# untitled.net
KiCad netlist of a schematic drawn in EAGLE
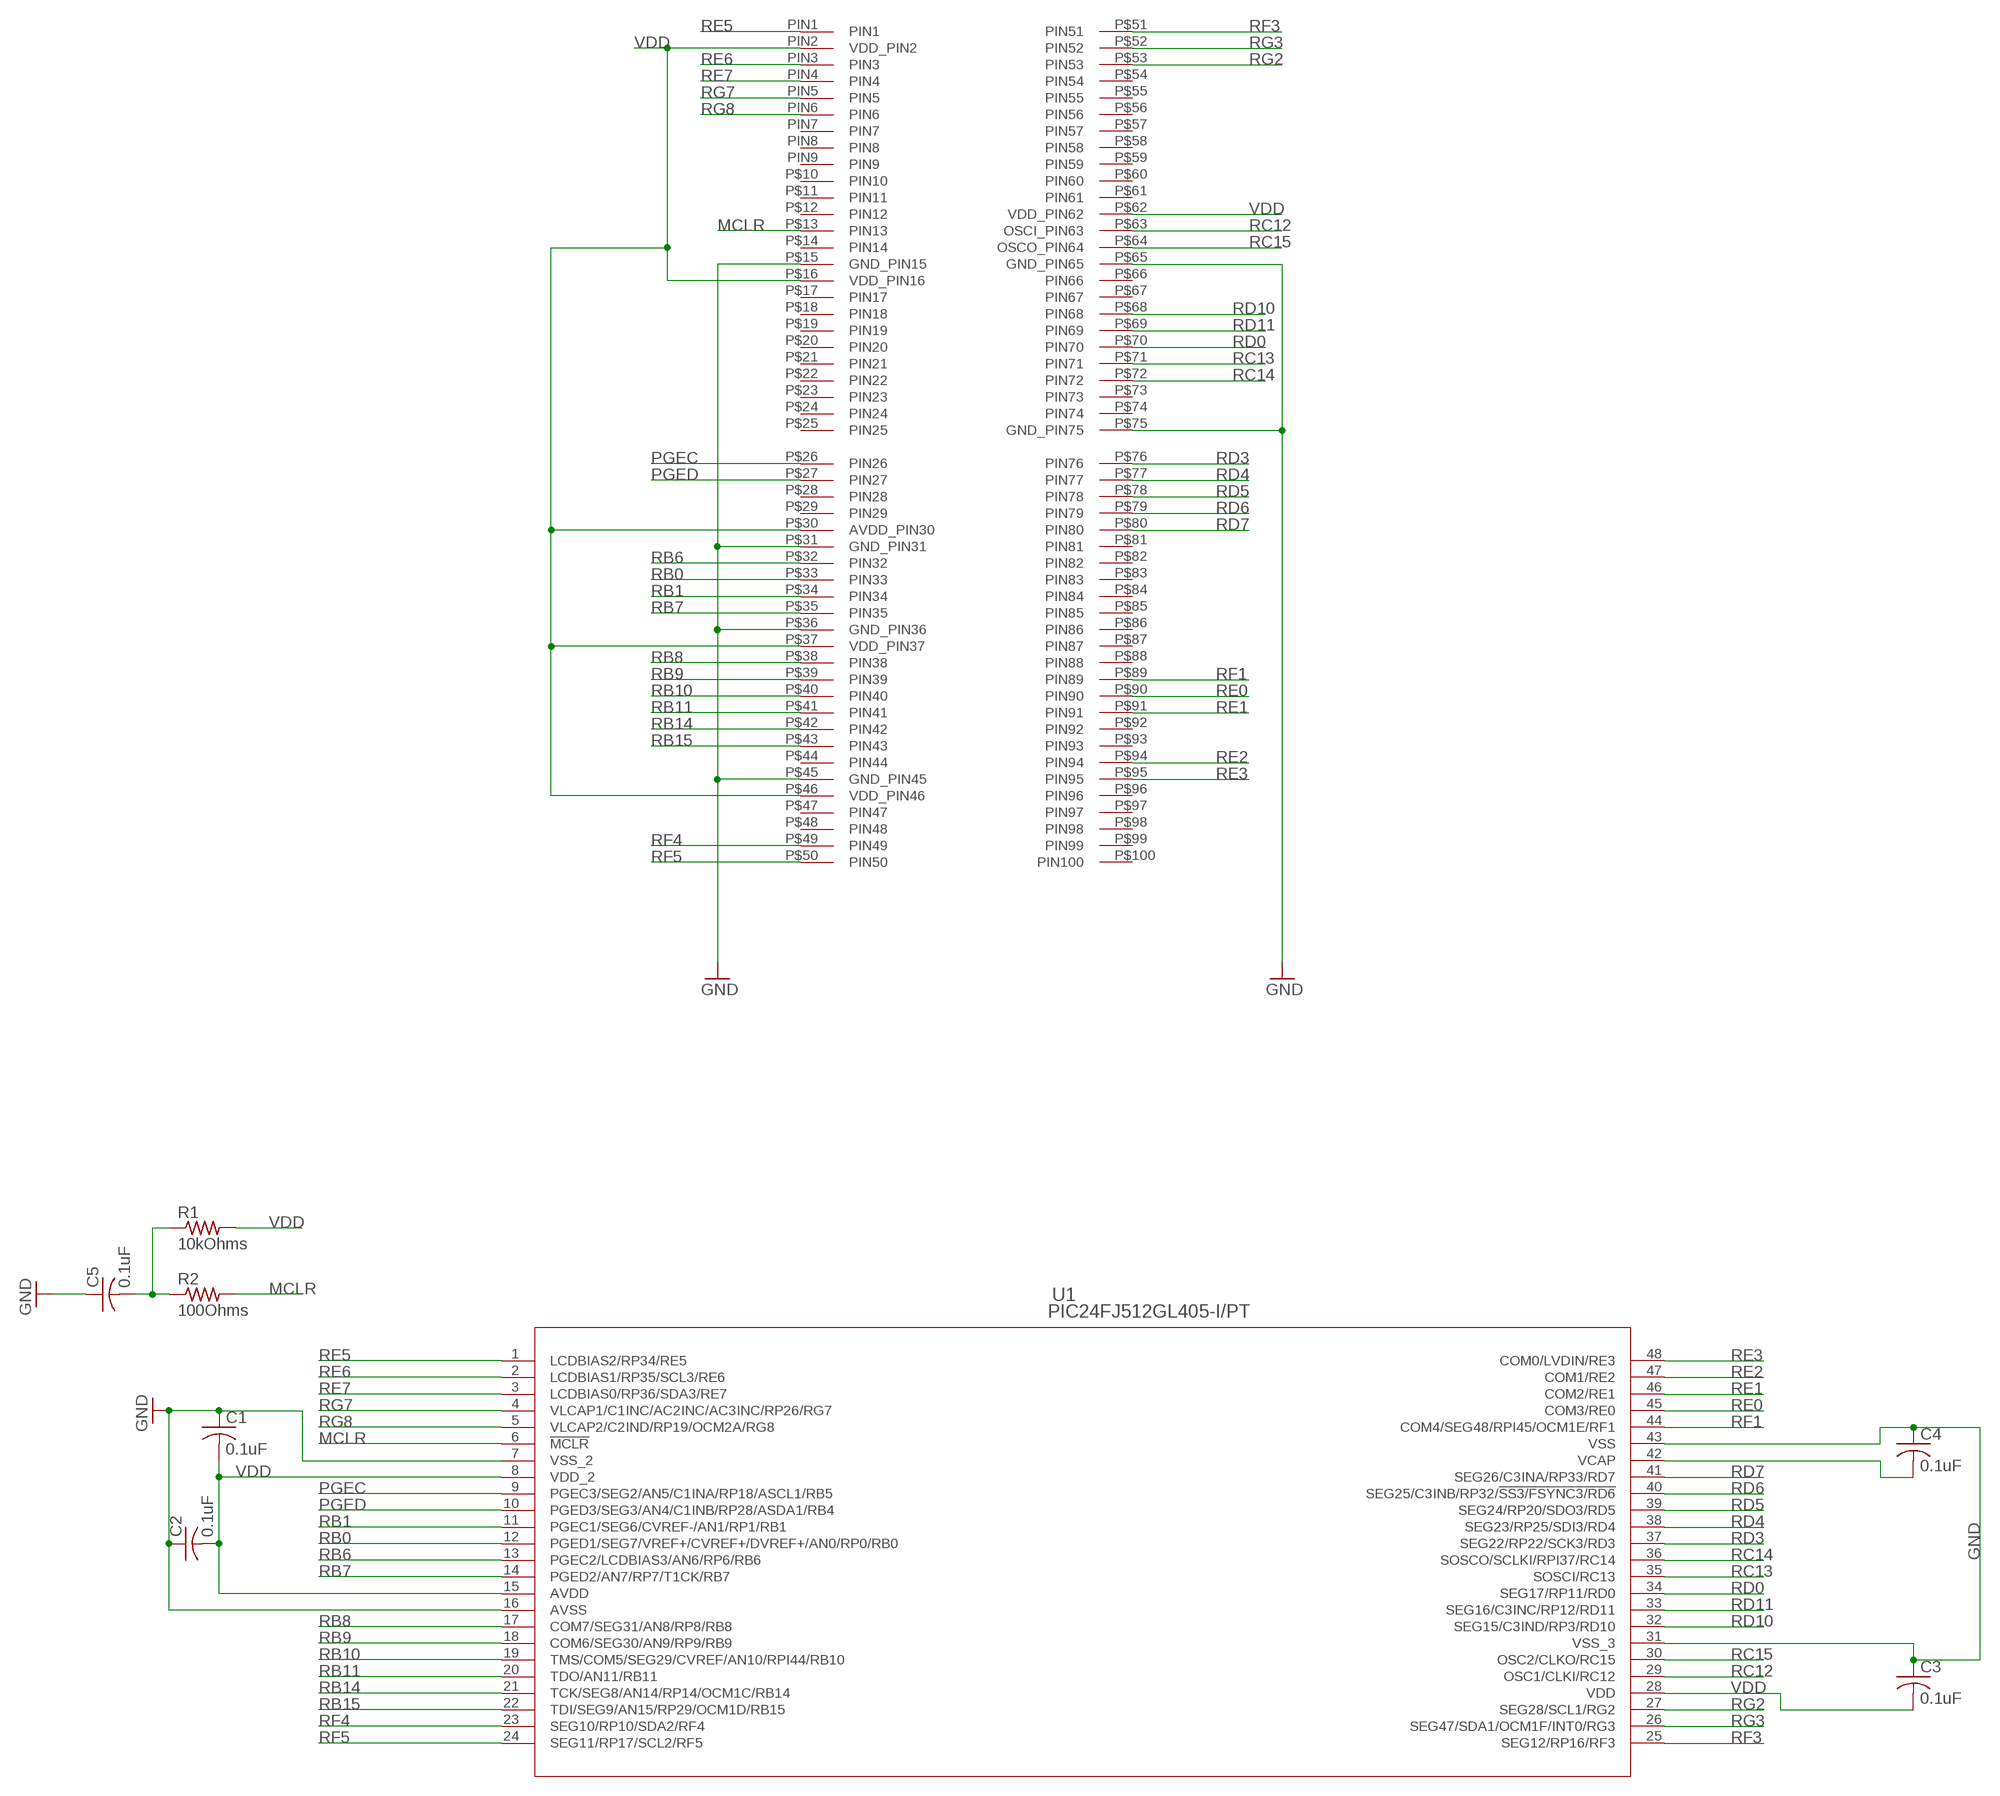
[diagram p0: schematic, sheet 1]

(export (version "E")
  (design (tool "Eeschema 10.0.6"))
  (components
    (comp (ref "C1")
      (value "0.1uF")
      (footprint "eagle-import:C0603")
      (libsource (lib "eagle-import") (part "C-USC0603"))
    )
    (comp (ref "C2")
      (value "0.1uF")
      (footprint "eagle-import:C0603")
      (libsource (lib "eagle-import") (part "C-USC0603"))
    )
    (comp (ref "C3")
      (value "0.1uF")
      (footprint "eagle-import:C0603")
      (libsource (lib "eagle-import") (part "C-USC0603"))
    )
    (comp (ref "C4")
      (value "0.1uF")
      (footprint "eagle-import:C0603")
      (libsource (lib "eagle-import") (part "C-USC0603"))
    )
    (comp (ref "C5")
      (value "0.1uF")
      (footprint "eagle-import:C0603")
      (libsource (lib "eagle-import") (part "C-USC0603"))
    )
    (comp (ref "R1")
      (value "10kOhms")
      (footprint "eagle-import:R0603")
      (libsource (lib "eagle-import") (part "R-US_R0603"))
    )
    (comp (ref "R2")
      (value "100Ohms")
      (footprint "eagle-import:R0603")
      (libsource (lib "eagle-import") (part "R-US_R0603"))
    )
    (comp (ref "U$1")
      (value "PIC_24_PIM_100")
      (footprint "eagle-import:PIC_PIM_100")
      (libsource (lib "eagle-import") (part "PIC_24_PIM_100"))
    )
    (comp (ref "U1")
      (value "PIC24FJ512GL405-I/PT")
      (footprint "eagle-import:TQFP48_PT_MCH")
      (fields (field (name "COPYRIGHT") "Copyright (C) 2023 Ultra Librarian. All rights reserved."))
      (libsource (lib "eagle-import") (part "PIC24FJ512GL405-I/PT"))
    )
  )
  (nets
    (net (code "1") (name "/MCLR") (class "Default")
      (node (ref "R2") (pin "2") (pinfunction "2_2") (pintype "passive"))
      (node (ref "U$1") (pin "P$13") (pinfunction "PIN13_P$13") (pintype "bidirectional"))
      (node (ref "U1") (pin "6") (pinfunction "~{MCLR}_6") (pintype "input"))
    )
    (net (code "2") (name "/PGEC") (class "Default")
      (node (ref "U$1") (pin "P$26") (pinfunction "PIN26_P$26") (pintype "bidirectional"))
      (node (ref "U1") (pin "9") (pinfunction "PGEC3/SEG2/AN5/C1INA/RP18/ASCL1/RB5_9") (pintype "bidirectional"))
    )
    (net (code "3") (name "/PGED") (class "Default")
      (node (ref "U$1") (pin "P$27") (pinfunction "PIN27_P$27") (pintype "bidirectional"))
      (node (ref "U1") (pin "10") (pinfunction "PGED3/SEG3/AN4/C1INB/RP28/ASDA1/RB4_10") (pintype "bidirectional"))
    )
    (net (code "4") (name "/RB0") (class "Default")
      (node (ref "U$1") (pin "P$33") (pinfunction "PIN33_P$33") (pintype "bidirectional"))
      (node (ref "U1") (pin "12") (pinfunction "PGED1/SEG7/VREF+/CVREF+/DVREF+/AN0/RP0/RB0_12") (pintype "bidirectional"))
    )
    (net (code "5") (name "/RB1") (class "Default")
      (node (ref "U$1") (pin "P$34") (pinfunction "PIN34_P$34") (pintype "bidirectional"))
      (node (ref "U1") (pin "11") (pinfunction "PGEC1/SEG6/CVREF-/AN1/RP1/RB1_11") (pintype "bidirectional"))
    )
    (net (code "6") (name "/RB6") (class "Default")
      (node (ref "U$1") (pin "P$32") (pinfunction "PIN32_P$32") (pintype "bidirectional"))
      (node (ref "U1") (pin "13") (pinfunction "PGEC2/LCDBIAS3/AN6/RP6/RB6_13") (pintype "bidirectional"))
    )
    (net (code "7") (name "/RB7") (class "Default")
      (node (ref "U$1") (pin "P$35") (pinfunction "PIN35_P$35") (pintype "bidirectional"))
      (node (ref "U1") (pin "14") (pinfunction "PGED2/AN7/RP7/T1CK/RB7_14") (pintype "bidirectional"))
    )
    (net (code "8") (name "/RB8") (class "Default")
      (node (ref "U$1") (pin "P$38") (pinfunction "PIN38_P$38") (pintype "bidirectional"))
      (node (ref "U1") (pin "17") (pinfunction "COM7/SEG31/AN8/RP8/RB8_17") (pintype "bidirectional"))
    )
    (net (code "9") (name "/RB9") (class "Default")
      (node (ref "U$1") (pin "P$39") (pinfunction "PIN39_P$39") (pintype "bidirectional"))
      (node (ref "U1") (pin "18") (pinfunction "COM6/SEG30/AN9/RP9/RB9_18") (pintype "bidirectional"))
    )
    (net (code "10") (name "/RB10") (class "Default")
      (node (ref "U$1") (pin "P$40") (pinfunction "PIN40_P$40") (pintype "bidirectional"))
      (node (ref "U1") (pin "19") (pinfunction "TMS/COM5/SEG29/CVREF/AN10/RPI44/RB10_19") (pintype "bidirectional"))
    )
    (net (code "11") (name "/RB11") (class "Default")
      (node (ref "U$1") (pin "P$41") (pinfunction "PIN41_P$41") (pintype "bidirectional"))
      (node (ref "U1") (pin "20") (pinfunction "TDO/AN11/RB11_20") (pintype "bidirectional"))
    )
    (net (code "12") (name "/RB14") (class "Default")
      (node (ref "U$1") (pin "P$42") (pinfunction "PIN42_P$42") (pintype "bidirectional"))
      (node (ref "U1") (pin "21") (pinfunction "TCK/SEG8/AN14/RP14/OCM1C/RB14_21") (pintype "bidirectional"))
    )
    (net (code "13") (name "/RB15") (class "Default")
      (node (ref "U$1") (pin "P$43") (pinfunction "PIN43_P$43") (pintype "bidirectional"))
      (node (ref "U1") (pin "22") (pinfunction "TDI/SEG9/AN15/RP29/OCM1D/RB15_22") (pintype "bidirectional"))
    )
    (net (code "14") (name "/RC12") (class "Default")
      (node (ref "U$1") (pin "P$63") (pinfunction "OSCI_PIN63_P$63") (pintype "bidirectional"))
      (node (ref "U1") (pin "29") (pinfunction "OSC1/CLKI/RC12_29") (pintype "bidirectional"))
    )
    (net (code "15") (name "/RC13") (class "Default")
      (node (ref "U$1") (pin "P$71") (pinfunction "PIN71_P$71") (pintype "bidirectional"))
      (node (ref "U1") (pin "35") (pinfunction "SOSCI/RC13_35") (pintype "bidirectional"))
    )
    (net (code "16") (name "/RC14") (class "Default")
      (node (ref "U$1") (pin "P$72") (pinfunction "PIN72_P$72") (pintype "bidirectional"))
      (node (ref "U1") (pin "36") (pinfunction "SOSCO/SCLKI/RPI37/RC14_36") (pintype "bidirectional"))
    )
    (net (code "17") (name "/RC15") (class "Default")
      (node (ref "U$1") (pin "P$64") (pinfunction "OSCO_PIN64_P$64") (pintype "bidirectional"))
      (node (ref "U1") (pin "30") (pinfunction "OSC2/CLKO/RC15_30") (pintype "bidirectional"))
    )
    (net (code "18") (name "/RD0") (class "Default")
      (node (ref "U$1") (pin "P$70") (pinfunction "PIN70_P$70") (pintype "bidirectional"))
      (node (ref "U1") (pin "34") (pinfunction "SEG17/RP11/RD0_34") (pintype "bidirectional"))
    )
    (net (code "19") (name "/RD3") (class "Default")
      (node (ref "U$1") (pin "P$76") (pinfunction "PIN76_P$76") (pintype "bidirectional"))
      (node (ref "U1") (pin "37") (pinfunction "SEG22/RP22/SCK3/RD3_37") (pintype "bidirectional"))
    )
    (net (code "20") (name "/RD4") (class "Default")
      (node (ref "U$1") (pin "P$77") (pinfunction "PIN77_P$77") (pintype "bidirectional"))
      (node (ref "U1") (pin "38") (pinfunction "SEG23/RP25/SDI3/RD4_38") (pintype "bidirectional"))
    )
    (net (code "21") (name "/RD5") (class "Default")
      (node (ref "U$1") (pin "P$78") (pinfunction "PIN78_P$78") (pintype "bidirectional"))
      (node (ref "U1") (pin "39") (pinfunction "SEG24/RP20/SDO3/RD5_39") (pintype "bidirectional"))
    )
    (net (code "22") (name "/RD6") (class "Default")
      (node (ref "U$1") (pin "P$79") (pinfunction "PIN79_P$79") (pintype "bidirectional"))
      (node (ref "U1") (pin "40") (pinfunction "SEG25/C3INB/RP32/~{SS3/FSYNC3/RD6}_40") (pintype "bidirectional"))
    )
    (net (code "23") (name "/RD7") (class "Default")
      (node (ref "U$1") (pin "P$80") (pinfunction "PIN80_P$80") (pintype "bidirectional"))
      (node (ref "U1") (pin "41") (pinfunction "SEG26/C3INA/RP33/RD7_41") (pintype "bidirectional"))
    )
    (net (code "24") (name "/RD10") (class "Default")
      (node (ref "U$1") (pin "P$68") (pinfunction "PIN68_P$68") (pintype "bidirectional"))
      (node (ref "U1") (pin "32") (pinfunction "SEG15/C3IND/RP3/RD10_32") (pintype "bidirectional"))
    )
    (net (code "25") (name "/RD11") (class "Default")
      (node (ref "U$1") (pin "P$69") (pinfunction "PIN69_P$69") (pintype "bidirectional"))
      (node (ref "U1") (pin "33") (pinfunction "SEG16/C3INC/RP12/RD11_33") (pintype "bidirectional"))
    )
    (net (code "26") (name "/RE0") (class "Default")
      (node (ref "U$1") (pin "P$90") (pinfunction "PIN90_P$90") (pintype "bidirectional"))
      (node (ref "U1") (pin "45") (pinfunction "COM3/RE0_45") (pintype "bidirectional"))
    )
    (net (code "27") (name "/RE1") (class "Default")
      (node (ref "U$1") (pin "P$91") (pinfunction "PIN91_P$91") (pintype "bidirectional"))
      (node (ref "U1") (pin "46") (pinfunction "COM2/RE1_46") (pintype "bidirectional"))
    )
    (net (code "28") (name "/RE2") (class "Default")
      (node (ref "U$1") (pin "P$94") (pinfunction "PIN94_P$94") (pintype "bidirectional"))
      (node (ref "U1") (pin "47") (pinfunction "COM1/RE2_47") (pintype "bidirectional"))
    )
    (net (code "29") (name "/RE3") (class "Default")
      (node (ref "U$1") (pin "P$95") (pinfunction "PIN95_P$95") (pintype "bidirectional"))
      (node (ref "U1") (pin "48") (pinfunction "COM0/LVDIN/RE3_48") (pintype "bidirectional"))
    )
    (net (code "30") (name "/RE5") (class "Default")
      (node (ref "U$1") (pin "PIN1") (pinfunction "PIN1_PIN1") (pintype "bidirectional"))
      (node (ref "U1") (pin "1") (pinfunction "LCDBIAS2/RP34/RE5_1") (pintype "bidirectional"))
    )
    (net (code "31") (name "/RE6") (class "Default")
      (node (ref "U$1") (pin "PIN3") (pinfunction "PIN3_PIN3") (pintype "bidirectional"))
      (node (ref "U1") (pin "2") (pinfunction "LCDBIAS1/RP35/SCL3/RE6_2") (pintype "bidirectional"))
    )
    (net (code "32") (name "/RE7") (class "Default")
      (node (ref "U$1") (pin "PIN4") (pinfunction "PIN4_PIN4") (pintype "bidirectional"))
      (node (ref "U1") (pin "3") (pinfunction "LCDBIAS0/RP36/SDA3/RE7_3") (pintype "bidirectional"))
    )
    (net (code "33") (name "/RF1") (class "Default")
      (node (ref "U$1") (pin "P$89") (pinfunction "PIN89_P$89") (pintype "bidirectional"))
      (node (ref "U1") (pin "44") (pinfunction "COM4/SEG48/RPI45/OCM1E/RF1_44") (pintype "bidirectional"))
    )
    (net (code "34") (name "/RF3") (class "Default")
      (node (ref "U$1") (pin "P$51") (pinfunction "PIN51_P$51") (pintype "bidirectional"))
      (node (ref "U1") (pin "25") (pinfunction "SEG12/RP16/RF3_25") (pintype "bidirectional"))
    )
    (net (code "35") (name "/RF4") (class "Default")
      (node (ref "U$1") (pin "P$49") (pinfunction "PIN49_P$49") (pintype "bidirectional"))
      (node (ref "U1") (pin "23") (pinfunction "SEG10/RP10/SDA2/RF4_23") (pintype "bidirectional"))
    )
    (net (code "36") (name "/RF5") (class "Default")
      (node (ref "U$1") (pin "P$50") (pinfunction "PIN50_P$50") (pintype "bidirectional"))
      (node (ref "U1") (pin "24") (pinfunction "SEG11/RP17/SCL2/RF5_24") (pintype "bidirectional"))
    )
    (net (code "37") (name "/RG2") (class "Default")
      (node (ref "U$1") (pin "P$53") (pinfunction "PIN53_P$53") (pintype "bidirectional"))
      (node (ref "U1") (pin "27") (pinfunction "SEG28/SCL1/RG2_27") (pintype "bidirectional"))
    )
    (net (code "38") (name "/RG3") (class "Default")
      (node (ref "U$1") (pin "P$52") (pinfunction "PIN52_P$52") (pintype "bidirectional"))
      (node (ref "U1") (pin "26") (pinfunction "SEG47/SDA1/OCM1F/INT0/RG3_26") (pintype "bidirectional"))
    )
    (net (code "39") (name "/RG7") (class "Default")
      (node (ref "U$1") (pin "PIN5") (pinfunction "PIN5_PIN5") (pintype "bidirectional"))
      (node (ref "U1") (pin "4") (pinfunction "VLCAP1/C1INC/AC2INC/AC3INC/RP26/RG7_4") (pintype "bidirectional"))
    )
    (net (code "40") (name "/RG8") (class "Default")
      (node (ref "U$1") (pin "PIN6") (pinfunction "PIN6_PIN6") (pintype "bidirectional"))
      (node (ref "U1") (pin "5") (pinfunction "VLCAP2/C2IND/RP19/OCM2A/RG8_5") (pintype "bidirectional"))
    )
    (net (code "41") (name "/VDD") (class "Default")
      (node (ref "C1") (pin "2") (pinfunction "2_2") (pintype "passive"))
      (node (ref "C2") (pin "2") (pinfunction "2_2") (pintype "passive"))
      (node (ref "C3") (pin "2") (pinfunction "2_2") (pintype "passive"))
      (node (ref "R1") (pin "2") (pinfunction "2_2") (pintype "passive"))
      (node (ref "U$1") (pin "P$16") (pinfunction "VDD_PIN16_P$16") (pintype "bidirectional"))
      (node (ref "U$1") (pin "P$30") (pinfunction "AVDD_PIN30_P$30") (pintype "bidirectional"))
      (node (ref "U$1") (pin "P$37") (pinfunction "VDD_PIN37_P$37") (pintype "bidirectional"))
      (node (ref "U$1") (pin "P$46") (pinfunction "VDD_PIN46_P$46") (pintype "bidirectional"))
      (node (ref "U$1") (pin "P$62") (pinfunction "VDD_PIN62_P$62") (pintype "bidirectional"))
      (node (ref "U$1") (pin "PIN2") (pinfunction "VDD_PIN2_PIN2") (pintype "bidirectional"))
      (node (ref "U1") (pin "15") (pinfunction "AVDD_15") (pintype "power_in"))
      (node (ref "U1") (pin "28") (pinfunction "VDD_28") (pintype "power_in"))
      (node (ref "U1") (pin "8") (pinfunction "VDD_2_8") (pintype "power_in"))
    )
    (net (code "42") (name "GND") (class "Default")
      (node (ref "C1") (pin "1") (pinfunction "1_1") (pintype "passive"))
      (node (ref "C2") (pin "1") (pinfunction "1_1") (pintype "passive"))
      (node (ref "C3") (pin "1") (pinfunction "1_1") (pintype "passive"))
      (node (ref "C4") (pin "1") (pinfunction "1_1") (pintype "passive"))
      (node (ref "C5") (pin "1") (pinfunction "1_1") (pintype "passive"))
      (node (ref "U$1") (pin "P$15") (pinfunction "GND_PIN15_P$15") (pintype "bidirectional"))
      (node (ref "U$1") (pin "P$31") (pinfunction "GND_PIN31_P$31") (pintype "bidirectional"))
      (node (ref "U$1") (pin "P$36") (pinfunction "GND_PIN36_P$36") (pintype "bidirectional"))
      (node (ref "U$1") (pin "P$45") (pinfunction "GND_PIN45_P$45") (pintype "bidirectional"))
      (node (ref "U$1") (pin "P$65") (pinfunction "GND_PIN65_P$65") (pintype "bidirectional"))
      (node (ref "U$1") (pin "P$75") (pinfunction "GND_PIN75_P$75") (pintype "bidirectional"))
      (node (ref "U1") (pin "16") (pinfunction "AVSS_16") (pintype "passive"))
      (node (ref "U1") (pin "31") (pinfunction "VSS_3_31") (pintype "passive"))
      (node (ref "U1") (pin "43") (pinfunction "VSS_43") (pintype "passive"))
      (node (ref "U1") (pin "7") (pinfunction "VSS_2_7") (pintype "passive"))
    )
    (net (code "43") (name "Net-(C5-Pad2)") (class "Default")
      (node (ref "C5") (pin "2") (pinfunction "2_2") (pintype "passive"))
      (node (ref "R1") (pin "1") (pinfunction "1_1") (pintype "passive"))
      (node (ref "R2") (pin "1") (pinfunction "1_1") (pintype "passive"))
    )
    (net (code "44") (name "Net-(U1-VCAP)") (class "Default")
      (node (ref "C4") (pin "2") (pinfunction "2_2") (pintype "passive"))
      (node (ref "U1") (pin "42") (pinfunction "VCAP_42") (pintype "power_in"))
    )
    (net (code "45") (name "unconnected-(U$1-PIN10-PadP$10)") (class "Default")
      (node (ref "U$1") (pin "P$10") (pinfunction "PIN10_P$10") (pintype "bidirectional"))
    )
    (net (code "46") (name "unconnected-(U$1-PIN11-PadP$11)") (class "Default")
      (node (ref "U$1") (pin "P$11") (pinfunction "PIN11_P$11") (pintype "bidirectional"))
    )
    (net (code "47") (name "unconnected-(U$1-PIN12-PadP$12)") (class "Default")
      (node (ref "U$1") (pin "P$12") (pinfunction "PIN12_P$12") (pintype "bidirectional"))
    )
    (net (code "48") (name "unconnected-(U$1-PIN14-PadP$14)") (class "Default")
      (node (ref "U$1") (pin "P$14") (pinfunction "PIN14_P$14") (pintype "bidirectional"))
    )
    (net (code "49") (name "unconnected-(U$1-PIN17-PadP$17)") (class "Default")
      (node (ref "U$1") (pin "P$17") (pinfunction "PIN17_P$17") (pintype "bidirectional"))
    )
    (net (code "50") (name "unconnected-(U$1-PIN18-PadP$18)") (class "Default")
      (node (ref "U$1") (pin "P$18") (pinfunction "PIN18_P$18") (pintype "bidirectional"))
    )
    (net (code "51") (name "unconnected-(U$1-PIN19-PadP$19)") (class "Default")
      (node (ref "U$1") (pin "P$19") (pinfunction "PIN19_P$19") (pintype "bidirectional"))
    )
    (net (code "52") (name "unconnected-(U$1-PIN20-PadP$20)") (class "Default")
      (node (ref "U$1") (pin "P$20") (pinfunction "PIN20_P$20") (pintype "bidirectional"))
    )
    (net (code "53") (name "unconnected-(U$1-PIN21-PadP$21)") (class "Default")
      (node (ref "U$1") (pin "P$21") (pinfunction "PIN21_P$21") (pintype "bidirectional"))
    )
    (net (code "54") (name "unconnected-(U$1-PIN22-PadP$22)") (class "Default")
      (node (ref "U$1") (pin "P$22") (pinfunction "PIN22_P$22") (pintype "bidirectional"))
    )
    (net (code "55") (name "unconnected-(U$1-PIN23-PadP$23)") (class "Default")
      (node (ref "U$1") (pin "P$23") (pinfunction "PIN23_P$23") (pintype "bidirectional"))
    )
    (net (code "56") (name "unconnected-(U$1-PIN24-PadP$24)") (class "Default")
      (node (ref "U$1") (pin "P$24") (pinfunction "PIN24_P$24") (pintype "bidirectional"))
    )
    (net (code "57") (name "unconnected-(U$1-PIN25-PadP$25)") (class "Default")
      (node (ref "U$1") (pin "P$25") (pinfunction "PIN25_P$25") (pintype "bidirectional"))
    )
    (net (code "58") (name "unconnected-(U$1-PIN28-PadP$28)") (class "Default")
      (node (ref "U$1") (pin "P$28") (pinfunction "PIN28_P$28") (pintype "bidirectional"))
    )
    (net (code "59") (name "unconnected-(U$1-PIN29-PadP$29)") (class "Default")
      (node (ref "U$1") (pin "P$29") (pinfunction "PIN29_P$29") (pintype "bidirectional"))
    )
    (net (code "60") (name "unconnected-(U$1-PIN44-PadP$44)") (class "Default")
      (node (ref "U$1") (pin "P$44") (pinfunction "PIN44_P$44") (pintype "bidirectional"))
    )
    (net (code "61") (name "unconnected-(U$1-PIN47-PadP$47)") (class "Default")
      (node (ref "U$1") (pin "P$47") (pinfunction "PIN47_P$47") (pintype "bidirectional"))
    )
    (net (code "62") (name "unconnected-(U$1-PIN48-PadP$48)") (class "Default")
      (node (ref "U$1") (pin "P$48") (pinfunction "PIN48_P$48") (pintype "bidirectional"))
    )
    (net (code "63") (name "unconnected-(U$1-PIN54-PadP$54)") (class "Default")
      (node (ref "U$1") (pin "P$54") (pinfunction "PIN54_P$54") (pintype "bidirectional"))
    )
    (net (code "64") (name "unconnected-(U$1-PIN55-PadP$55)") (class "Default")
      (node (ref "U$1") (pin "P$55") (pinfunction "PIN55_P$55") (pintype "bidirectional"))
    )
    (net (code "65") (name "unconnected-(U$1-PIN56-PadP$56)") (class "Default")
      (node (ref "U$1") (pin "P$56") (pinfunction "PIN56_P$56") (pintype "bidirectional"))
    )
    (net (code "66") (name "unconnected-(U$1-PIN57-PadP$57)") (class "Default")
      (node (ref "U$1") (pin "P$57") (pinfunction "PIN57_P$57") (pintype "bidirectional"))
    )
    (net (code "67") (name "unconnected-(U$1-PIN58-PadP$58)") (class "Default")
      (node (ref "U$1") (pin "P$58") (pinfunction "PIN58_P$58") (pintype "bidirectional"))
    )
    (net (code "68") (name "unconnected-(U$1-PIN59-PadP$59)") (class "Default")
      (node (ref "U$1") (pin "P$59") (pinfunction "PIN59_P$59") (pintype "bidirectional"))
    )
    (net (code "69") (name "unconnected-(U$1-PIN60-PadP$60)") (class "Default")
      (node (ref "U$1") (pin "P$60") (pinfunction "PIN60_P$60") (pintype "bidirectional"))
    )
    (net (code "70") (name "unconnected-(U$1-PIN61-PadP$61)") (class "Default")
      (node (ref "U$1") (pin "P$61") (pinfunction "PIN61_P$61") (pintype "bidirectional"))
    )
    (net (code "71") (name "unconnected-(U$1-PIN66-PadP$66)") (class "Default")
      (node (ref "U$1") (pin "P$66") (pinfunction "PIN66_P$66") (pintype "bidirectional"))
    )
    (net (code "72") (name "unconnected-(U$1-PIN67-PadP$67)") (class "Default")
      (node (ref "U$1") (pin "P$67") (pinfunction "PIN67_P$67") (pintype "bidirectional"))
    )
    (net (code "73") (name "unconnected-(U$1-PIN73-PadP$73)") (class "Default")
      (node (ref "U$1") (pin "P$73") (pinfunction "PIN73_P$73") (pintype "bidirectional"))
    )
    (net (code "74") (name "unconnected-(U$1-PIN74-PadP$74)") (class "Default")
      (node (ref "U$1") (pin "P$74") (pinfunction "PIN74_P$74") (pintype "bidirectional"))
    )
    (net (code "75") (name "unconnected-(U$1-PIN81-PadP$81)") (class "Default")
      (node (ref "U$1") (pin "P$81") (pinfunction "PIN81_P$81") (pintype "bidirectional"))
    )
    (net (code "76") (name "unconnected-(U$1-PIN82-PadP$82)") (class "Default")
      (node (ref "U$1") (pin "P$82") (pinfunction "PIN82_P$82") (pintype "bidirectional"))
    )
    (net (code "77") (name "unconnected-(U$1-PIN83-PadP$83)") (class "Default")
      (node (ref "U$1") (pin "P$83") (pinfunction "PIN83_P$83") (pintype "bidirectional"))
    )
    (net (code "78") (name "unconnected-(U$1-PIN84-PadP$84)") (class "Default")
      (node (ref "U$1") (pin "P$84") (pinfunction "PIN84_P$84") (pintype "bidirectional"))
    )
    (net (code "79") (name "unconnected-(U$1-PIN85-PadP$85)") (class "Default")
      (node (ref "U$1") (pin "P$85") (pinfunction "PIN85_P$85") (pintype "bidirectional"))
    )
    (net (code "80") (name "unconnected-(U$1-PIN86-PadP$86)") (class "Default")
      (node (ref "U$1") (pin "P$86") (pinfunction "PIN86_P$86") (pintype "bidirectional"))
    )
    (net (code "81") (name "unconnected-(U$1-PIN87-PadP$87)") (class "Default")
      (node (ref "U$1") (pin "P$87") (pinfunction "PIN87_P$87") (pintype "bidirectional"))
    )
    (net (code "82") (name "unconnected-(U$1-PIN88-PadP$88)") (class "Default")
      (node (ref "U$1") (pin "P$88") (pinfunction "PIN88_P$88") (pintype "bidirectional"))
    )
    (net (code "83") (name "unconnected-(U$1-PIN92-PadP$92)") (class "Default")
      (node (ref "U$1") (pin "P$92") (pinfunction "PIN92_P$92") (pintype "bidirectional"))
    )
    (net (code "84") (name "unconnected-(U$1-PIN93-PadP$93)") (class "Default")
      (node (ref "U$1") (pin "P$93") (pinfunction "PIN93_P$93") (pintype "bidirectional"))
    )
    (net (code "85") (name "unconnected-(U$1-PIN96-PadP$96)") (class "Default")
      (node (ref "U$1") (pin "P$96") (pinfunction "PIN96_P$96") (pintype "bidirectional"))
    )
    (net (code "86") (name "unconnected-(U$1-PIN97-PadP$97)") (class "Default")
      (node (ref "U$1") (pin "P$97") (pinfunction "PIN97_P$97") (pintype "bidirectional"))
    )
    (net (code "87") (name "unconnected-(U$1-PIN98-PadP$98)") (class "Default")
      (node (ref "U$1") (pin "P$98") (pinfunction "PIN98_P$98") (pintype "bidirectional"))
    )
    (net (code "88") (name "unconnected-(U$1-PIN99-PadP$99)") (class "Default")
      (node (ref "U$1") (pin "P$99") (pinfunction "PIN99_P$99") (pintype "bidirectional"))
    )
    (net (code "89") (name "unconnected-(U$1-PIN100-PadP$100)") (class "Default")
      (node (ref "U$1") (pin "P$100") (pinfunction "PIN100_P$100") (pintype "bidirectional"))
    )
    (net (code "90") (name "unconnected-(U$1-PadPIN7)") (class "Default")
      (node (ref "U$1") (pin "PIN7") (pinfunction "PIN7_PIN7") (pintype "bidirectional"))
    )
    (net (code "91") (name "unconnected-(U$1-PadPIN8)") (class "Default")
      (node (ref "U$1") (pin "PIN8") (pinfunction "PIN8_PIN8") (pintype "bidirectional"))
    )
    (net (code "92") (name "unconnected-(U$1-PadPIN9)") (class "Default")
      (node (ref "U$1") (pin "PIN9") (pinfunction "PIN9_PIN9") (pintype "bidirectional"))
    )
  )
)
